# schematic.net
KiCad netlist of a schematic drawn in EasyEDA
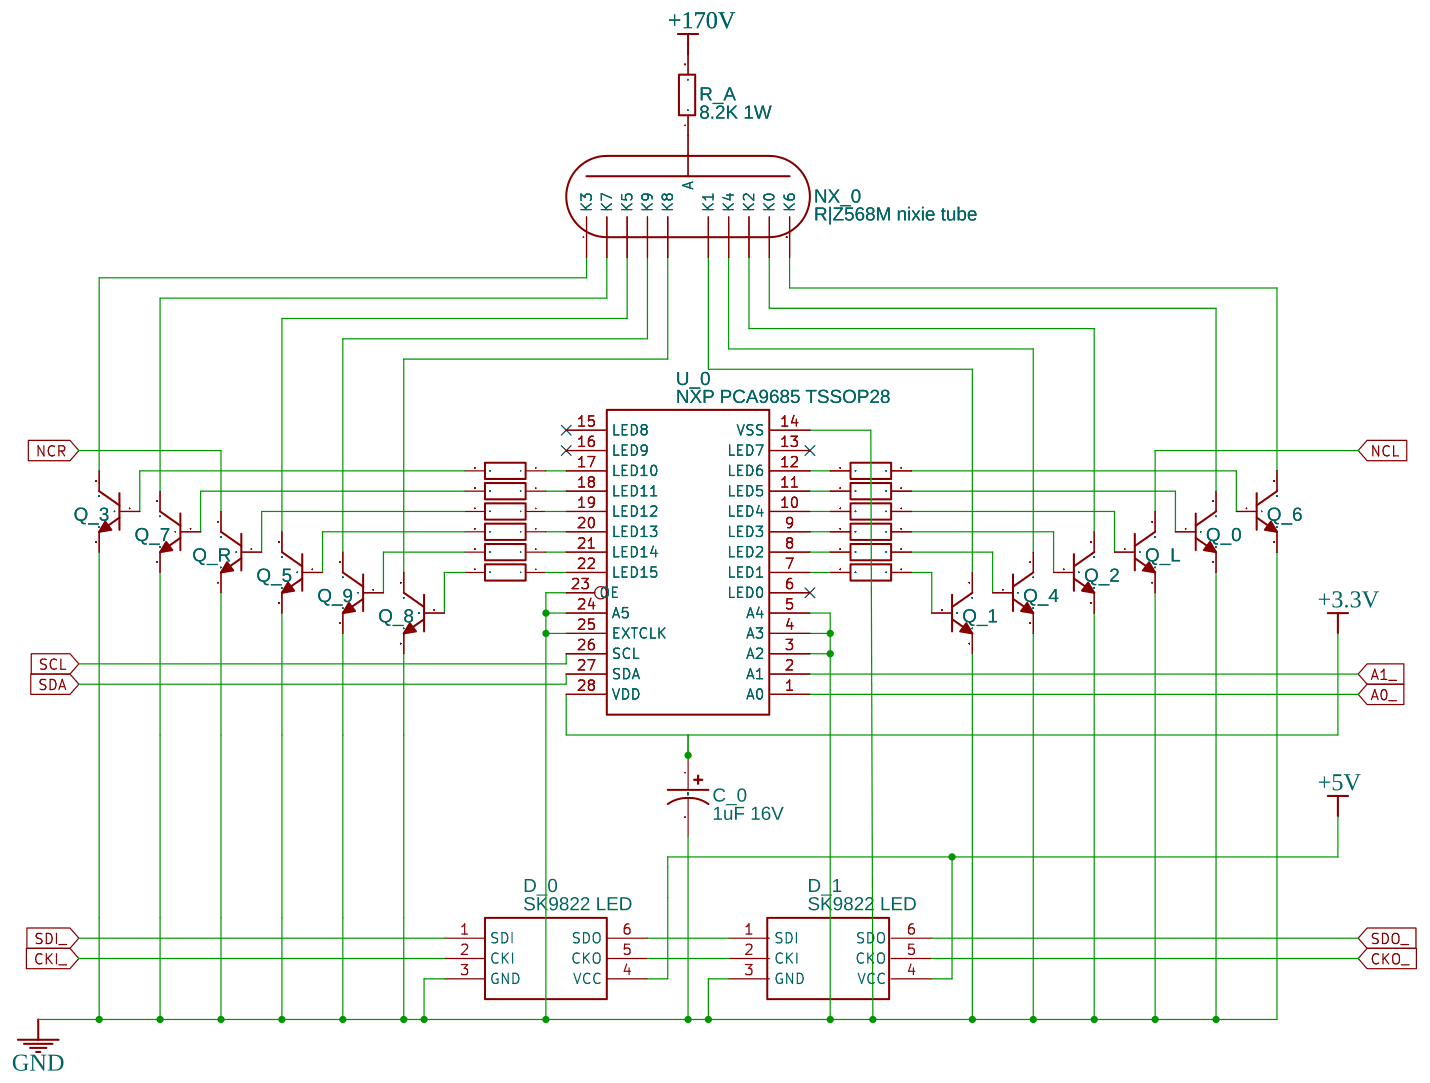
[diagram p0: schematic sheet]

(export (version "E")
  (design (tool "Eeschema 10.0.6"))
  (components
    (comp (ref "C_0")
      (value "1uF 16V")
      (fields
        (field (name "BOM_Manufacturer Part") "C0603C105K8RACTU")
        (field (name "BOM_Supplier Part") "399-11133-1-ND")
      )
      (libsource (lib "") (part "C_Tan_SMD_A_US"))
    )
    (comp (ref "D_0")
      (value "SK9822 LED")
      (fields (field (name "BOM_Manufacturer Part") "2343") (field (name "BOM_Supplier Part") "1528-1436-ND"))
      (libsource (lib "") (part "SK9822 LED"))
    )
    (comp (ref "D_1")
      (value "SK9822 LED")
      (fields (field (name "BOM_Manufacturer Part") "2343") (field (name "BOM_Supplier Part") "1528-1436-ND"))
      (libsource (lib "") (part "SK9822 LED_1"))
    )
    (comp (ref "NX_0") (value "R|Z568M nixie tube") (libsource (lib "") (part "R|Z568M nixie tube")))
    (comp (ref "Q_0")
      (value "SMMBTA42LT1G")
      (fields (field (name "BOM_Supplier Part") "SMMBTA42LT1GOSCT-ND"))
      (libsource (lib "") (part "MMBTA42LT1G"))
    )
    (comp (ref "Q_1")
      (value "SMMBTA42LT1G")
      (fields (field (name "BOM_Supplier Part") "SMMBTA42LT1GOSCT-ND"))
      (libsource (lib "") (part "MMBTA42LT1G"))
    )
    (comp (ref "Q_2")
      (value "SMMBTA42LT1G")
      (fields (field (name "BOM_Supplier Part") "SMMBTA42LT1GOSCT-ND"))
      (libsource (lib "") (part "MMBTA42LT1G"))
    )
    (comp (ref "Q_3")
      (value "SMMBTA42LT1G")
      (fields (field (name "BOM_Supplier Part") "SMMBTA42LT1GOSCT-ND"))
      (libsource (lib "") (part "MMBTA42LT1G_2"))
    )
    (comp (ref "Q_4")
      (value "SMMBTA42LT1G")
      (fields (field (name "BOM_Supplier Part") "SMMBTA42LT1GOSCT-ND"))
      (libsource (lib "") (part "MMBTA42LT1G"))
    )
    (comp (ref "Q_5")
      (value "SMMBTA42LT1G")
      (fields (field (name "BOM_Supplier Part") "SMMBTA42LT1GOSCT-ND"))
      (libsource (lib "") (part "MMBTA42LT1G_2"))
    )
    (comp (ref "Q_6")
      (value "SMMBTA42LT1G")
      (fields (field (name "BOM_Supplier Part") "SMMBTA42LT1GOSCT-ND"))
      (libsource (lib "") (part "MMBTA42LT1G"))
    )
    (comp (ref "Q_7")
      (value "SMMBTA42LT1G")
      (fields (field (name "BOM_Supplier Part") "SMMBTA42LT1GOSCT-ND"))
      (libsource (lib "") (part "MMBTA42LT1G_2"))
    )
    (comp (ref "Q_8")
      (value "SMMBTA42LT1G")
      (fields (field (name "BOM_Supplier Part") "SMMBTA42LT1GOSCT-ND"))
      (libsource (lib "") (part "MMBTA42LT1G_2"))
    )
    (comp (ref "Q_9")
      (value "SMMBTA42LT1G")
      (fields (field (name "BOM_Supplier Part") "SMMBTA42LT1GOSCT-ND"))
      (libsource (lib "") (part "MMBTA42LT1G_2"))
    )
    (comp (ref "Q_L")
      (value "SMMBTA42LT1G")
      (fields (field (name "BOM_Supplier Part") "SMMBTA42LT1GOSCT-ND"))
      (libsource (lib "") (part "MMBTA42LT1G_3"))
    )
    (comp (ref "Q_R")
      (value "SMMBTA42LT1G")
      (fields (field (name "BOM_Supplier Part") "SMMBTA42LT1GOSCT-ND"))
      (libsource (lib "") (part "MMBTA42LT1G_1"))
    )
    (comp (ref "R_0")
      (value "1K 1/10W")
      (fields
        (field (name "BOM_Manufacturer Part") "CRCW06031K00FKEA")
        (field (name "BOM_Supplier Part") "541-1.00KHCT-ND")
      )
      (libsource (lib "") (part "CR0805-FX-1001ELF"))
    )
    (comp (ref "R_1")
      (value "1K 1/10W")
      (fields
        (field (name "BOM_Manufacturer Part") "CRCW06031K00FKEA")
        (field (name "BOM_Supplier Part") "541-1.00KHCT-ND")
      )
      (libsource (lib "") (part "CR0805-FX-1001ELF"))
    )
    (comp (ref "R_2")
      (value "1K 1/10W")
      (fields
        (field (name "BOM_Manufacturer Part") "CRCW06031K00FKEA")
        (field (name "BOM_Supplier Part") "541-1.00KHCT-ND")
      )
      (libsource (lib "") (part "CR0805-FX-1001ELF"))
    )
    (comp (ref "R_3")
      (value "1K 1/10W")
      (fields
        (field (name "BOM_Manufacturer Part") "CRCW06031K00FKEA")
        (field (name "BOM_Supplier Part") "541-1.00KHCT-ND")
      )
      (libsource (lib "") (part "CR0805-FX-1001ELF"))
    )
    (comp (ref "R_4")
      (value "1K 1/10W")
      (fields
        (field (name "BOM_Manufacturer Part") "CRCW06031K00FKEA")
        (field (name "BOM_Supplier Part") "541-1.00KHCT-ND")
      )
      (libsource (lib "") (part "CR0805-FX-1001ELF"))
    )
    (comp (ref "R_5")
      (value "1K 1/10W")
      (fields
        (field (name "BOM_Manufacturer Part") "CRCW06031K00FKEA")
        (field (name "BOM_Supplier Part") "541-1.00KHCT-ND")
      )
      (libsource (lib "") (part "CR0805-FX-1001ELF"))
    )
    (comp (ref "R_6")
      (value "1K 1/10W")
      (fields
        (field (name "BOM_Manufacturer Part") "CRCW06031K00FKEA")
        (field (name "BOM_Supplier Part") "541-1.00KHCT-ND")
      )
      (libsource (lib "") (part "CR0805-FX-1001ELF"))
    )
    (comp (ref "R_7")
      (value "1K 1/10W")
      (fields
        (field (name "BOM_Manufacturer Part") "CRCW06031K00FKEA")
        (field (name "BOM_Supplier Part") "541-1.00KHCT-ND")
      )
      (libsource (lib "") (part "CR0805-FX-1001ELF"))
    )
    (comp (ref "R_8")
      (value "1K 1/10W")
      (fields
        (field (name "BOM_Manufacturer Part") "CRCW06031K00FKEA")
        (field (name "BOM_Supplier Part") "541-1.00KHCT-ND")
      )
      (libsource (lib "") (part "CR0805-FX-1001ELF"))
    )
    (comp (ref "R_9")
      (value "1K 1/10W")
      (fields
        (field (name "BOM_Manufacturer Part") "CRCW06031K00FKEA")
        (field (name "BOM_Supplier Part") "541-1.00KHCT-ND")
      )
      (libsource (lib "") (part "CR0805-FX-1001ELF"))
    )
    (comp (ref "R_A")
      (value "8.2K 1W")
      (fields
        (field (name "BOM_Manufacturer Part") "CRCW25128K20JNEG")
        (field (name "BOM_Supplier Part") "541-8.2KXCT-ND")
      )
      (libsource (lib "") (part "CR2512F8K2E04"))
    )
    (comp (ref "R_L")
      (value "1K 1/10W")
      (fields
        (field (name "BOM_Manufacturer Part") "CRCW06031K00FKEA")
        (field (name "BOM_Supplier Part") "541-1.00KHCT-ND")
      )
      (libsource (lib "") (part "CR0805-FX-1001ELF_1"))
    )
    (comp (ref "R_R")
      (value "1K 1/10W")
      (fields
        (field (name "BOM_Manufacturer Part") "CRCW06031K00FKEA")
        (field (name "BOM_Supplier Part") "541-1.00KHCT-ND")
      )
      (libsource (lib "") (part "CR0805-FX-1001ELF_2"))
    )
    (comp (ref "U_0")
      (value "NXP PCA9685 TSSOP28")
      (fields
        (field (name "BOM_Manufacturer Part") "PCA9685PW/Q900,118")
        (field (name "BOM_Supplier Part") "568-5931-1-ND")
      )
      (libsource (lib "") (part "NXP PCA9685 TSSOP28"))
    )
  )
  (nets
    (net (code "1") (name "+3.3V") (class "Default")
      (node (ref "C_0") (pin "1") (pinfunction "1_1") (pintype "unspecified"))
      (node (ref "U_0") (pin "28") (pinfunction "VDD_28") (pintype "unspecified"))
    )
    (net (code "2") (name "+5V") (class "Default")
      (node (ref "D_0") (pin "4") (pinfunction "VCC_4") (pintype "unspecified"))
      (node (ref "D_1") (pin "4") (pinfunction "VCC_4") (pintype "unspecified"))
    )
    (net (code "3") (name "+170V") (class "Default")
      (node (ref "R_A") (pin "2") (pinfunction "2_2") (pintype "unspecified"))
    )
    (net (code "4") (name "A0_") (class "Default")
      (node (ref "U_0") (pin "1") (pinfunction "A0_1") (pintype "unspecified"))
    )
    (net (code "5") (name "A1_") (class "Default")
      (node (ref "U_0") (pin "2") (pinfunction "A1_2") (pintype "unspecified"))
    )
    (net (code "6") (name "CKI_") (class "Default")
      (node (ref "D_0") (pin "2") (pinfunction "CKI_2") (pintype "unspecified"))
    )
    (net (code "7") (name "CKO_") (class "Default")
      (node (ref "D_1") (pin "5") (pinfunction "CKO_5") (pintype "unspecified"))
    )
    (net (code "8") (name "GND") (class "Default")
      (node (ref "C_0") (pin "2") (pinfunction "2_2") (pintype "unspecified"))
      (node (ref "D_0") (pin "3") (pinfunction "GND_3") (pintype "unspecified"))
      (node (ref "D_1") (pin "3") (pinfunction "GND_3") (pintype "unspecified"))
      (node (ref "Q_0") (pin "2") (pinfunction "2_2") (pintype "input"))
      (node (ref "Q_1") (pin "2") (pinfunction "2_2") (pintype "input"))
      (node (ref "Q_2") (pin "2") (pinfunction "2_2") (pintype "input"))
      (node (ref "Q_3") (pin "2") (pinfunction "2_2") (pintype "input"))
      (node (ref "Q_4") (pin "2") (pinfunction "2_2") (pintype "input"))
      (node (ref "Q_5") (pin "2") (pinfunction "2_2") (pintype "input"))
      (node (ref "Q_6") (pin "2") (pinfunction "2_2") (pintype "input"))
      (node (ref "Q_7") (pin "2") (pinfunction "2_2") (pintype "input"))
      (node (ref "Q_8") (pin "2") (pinfunction "2_2") (pintype "input"))
      (node (ref "Q_9") (pin "2") (pinfunction "2_2") (pintype "input"))
      (node (ref "Q_L") (pin "2") (pinfunction "2_2") (pintype "input"))
      (node (ref "Q_R") (pin "2") (pinfunction "2_2") (pintype "input"))
      (node (ref "U_0") (pin "14") (pinfunction "VSS_14") (pintype "unspecified"))
      (node (ref "U_0") (pin "23") (pinfunction "OE_23") (pintype "unspecified"))
      (node (ref "U_0") (pin "24") (pinfunction "A5_24") (pintype "unspecified"))
      (node (ref "U_0") (pin "25") (pinfunction "EXTCLK_25") (pintype "unspecified"))
      (node (ref "U_0") (pin "3") (pinfunction "A2_3") (pintype "unspecified"))
      (node (ref "U_0") (pin "4") (pinfunction "A3_4") (pintype "unspecified"))
      (node (ref "U_0") (pin "5") (pinfunction "A4_5") (pintype "unspecified"))
    )
    (net (code "9") (name "NCL") (class "Default")
      (node (ref "Q_L") (pin "3") (pinfunction "3_3") (pintype "input"))
    )
    (net (code "10") (name "NCR") (class "Default")
      (node (ref "Q_R") (pin "3") (pinfunction "3_3") (pintype "input"))
    )
    (net (code "11") (name "Net-(D_0-CKO)") (class "Default")
      (node (ref "D_0") (pin "5") (pinfunction "CKO_5") (pintype "unspecified"))
      (node (ref "D_1") (pin "2") (pinfunction "CKI_2") (pintype "unspecified"))
    )
    (net (code "12") (name "Net-(D_0-SDO)") (class "Default")
      (node (ref "D_0") (pin "6") (pinfunction "SDO_6") (pintype "unspecified"))
      (node (ref "D_1") (pin "1") (pinfunction "SDI_1") (pintype "unspecified"))
    )
    (net (code "13") (name "Net-(NX_0-A)") (class "Default")
      (node (ref "NX_0") (pin "6") (pinfunction "A_6") (pintype "unspecified"))
      (node (ref "R_A") (pin "1") (pinfunction "1_1") (pintype "unspecified"))
    )
    (net (code "14") (name "Net-(NX_0-K0)") (class "Default")
      (node (ref "NX_0") (pin "4") (pinfunction "K0_4") (pintype "unspecified"))
      (node (ref "Q_0") (pin "3") (pinfunction "3_3") (pintype "input"))
    )
    (net (code "15") (name "Net-(NX_0-K1)") (class "Default")
      (node (ref "NX_0") (pin "1") (pinfunction "K1_1") (pintype "passive"))
      (node (ref "Q_1") (pin "3") (pinfunction "3_3") (pintype "input"))
    )
    (net (code "16") (name "Net-(NX_0-K2)") (class "Default")
      (node (ref "NX_0") (pin "3") (pinfunction "K2_3") (pintype "unspecified"))
      (node (ref "Q_2") (pin "3") (pinfunction "3_3") (pintype "input"))
    )
    (net (code "17") (name "Net-(NX_0-K3)") (class "Default")
      (node (ref "NX_0") (pin "7") (pinfunction "K3_7") (pintype "unspecified"))
      (node (ref "Q_3") (pin "3") (pinfunction "3_3") (pintype "input"))
    )
    (net (code "18") (name "Net-(NX_0-K4)") (class "Default")
      (node (ref "NX_0") (pin "2") (pinfunction "K4_2") (pintype "unspecified"))
      (node (ref "Q_4") (pin "3") (pinfunction "3_3") (pintype "input"))
    )
    (net (code "19") (name "Net-(NX_0-K5)") (class "Default")
      (node (ref "NX_0") (pin "9") (pinfunction "K5_9") (pintype "unspecified"))
      (node (ref "Q_5") (pin "3") (pinfunction "3_3") (pintype "input"))
    )
    (net (code "20") (name "Net-(NX_0-K6)") (class "Default")
      (node (ref "NX_0") (pin "5") (pinfunction "K6_5") (pintype "unspecified"))
      (node (ref "Q_6") (pin "3") (pinfunction "3_3") (pintype "input"))
    )
    (net (code "21") (name "Net-(NX_0-K7)") (class "Default")
      (node (ref "NX_0") (pin "8") (pinfunction "K7_8") (pintype "unspecified"))
      (node (ref "Q_7") (pin "3") (pinfunction "3_3") (pintype "input"))
    )
    (net (code "22") (name "Net-(NX_0-K8)") (class "Default")
      (node (ref "NX_0") (pin "11") (pinfunction "K8_11") (pintype "unspecified"))
      (node (ref "Q_8") (pin "3") (pinfunction "3_3") (pintype "input"))
    )
    (net (code "23") (name "Net-(NX_0-K9)") (class "Default")
      (node (ref "NX_0") (pin "10") (pinfunction "K9_10") (pintype "unspecified"))
      (node (ref "Q_9") (pin "3") (pinfunction "3_3") (pintype "input"))
    )
    (net (code "24") (name "Net-(Q_0-Pad1)") (class "Default")
      (node (ref "Q_0") (pin "1") (pinfunction "1_1") (pintype "input"))
      (node (ref "R_0") (pin "1") (pinfunction "1_1") (pintype "unspecified"))
    )
    (net (code "25") (name "Net-(Q_1-Pad1)") (class "Default")
      (node (ref "Q_1") (pin "1") (pinfunction "1_1") (pintype "input"))
      (node (ref "R_1") (pin "1") (pinfunction "1_1") (pintype "unspecified"))
    )
    (net (code "26") (name "Net-(Q_2-Pad1)") (class "Default")
      (node (ref "Q_2") (pin "1") (pinfunction "1_1") (pintype "input"))
      (node (ref "R_2") (pin "1") (pinfunction "1_1") (pintype "unspecified"))
    )
    (net (code "27") (name "Net-(Q_3-Pad1)") (class "Default")
      (node (ref "Q_3") (pin "1") (pinfunction "1_1") (pintype "input"))
      (node (ref "R_3") (pin "2") (pinfunction "2_2") (pintype "unspecified"))
    )
    (net (code "28") (name "Net-(Q_4-Pad1)") (class "Default")
      (node (ref "Q_4") (pin "1") (pinfunction "1_1") (pintype "input"))
      (node (ref "R_4") (pin "1") (pinfunction "1_1") (pintype "unspecified"))
    )
    (net (code "29") (name "Net-(Q_5-Pad1)") (class "Default")
      (node (ref "Q_5") (pin "1") (pinfunction "1_1") (pintype "input"))
      (node (ref "R_5") (pin "2") (pinfunction "2_2") (pintype "unspecified"))
    )
    (net (code "30") (name "Net-(Q_6-Pad1)") (class "Default")
      (node (ref "Q_6") (pin "1") (pinfunction "1_1") (pintype "input"))
      (node (ref "R_6") (pin "1") (pinfunction "1_1") (pintype "unspecified"))
    )
    (net (code "31") (name "Net-(Q_7-Pad1)") (class "Default")
      (node (ref "Q_7") (pin "1") (pinfunction "1_1") (pintype "input"))
      (node (ref "R_7") (pin "2") (pinfunction "2_2") (pintype "unspecified"))
    )
    (net (code "32") (name "Net-(Q_8-Pad1)") (class "Default")
      (node (ref "Q_8") (pin "1") (pinfunction "1_1") (pintype "input"))
      (node (ref "R_8") (pin "2") (pinfunction "2_2") (pintype "unspecified"))
    )
    (net (code "33") (name "Net-(Q_9-Pad1)") (class "Default")
      (node (ref "Q_9") (pin "1") (pinfunction "1_1") (pintype "input"))
      (node (ref "R_9") (pin "2") (pinfunction "2_2") (pintype "unspecified"))
    )
    (net (code "34") (name "Net-(Q_L-Pad1)") (class "Default")
      (node (ref "Q_L") (pin "1") (pinfunction "1_1") (pintype "input"))
      (node (ref "R_L") (pin "1") (pinfunction "1_1") (pintype "unspecified"))
    )
    (net (code "35") (name "Net-(Q_R-Pad1)") (class "Default")
      (node (ref "Q_R") (pin "1") (pinfunction "1_1") (pintype "input"))
      (node (ref "R_R") (pin "2") (pinfunction "2_2") (pintype "unspecified"))
    )
    (net (code "36") (name "Net-(U_0-LED1)") (class "Default")
      (node (ref "R_1") (pin "2") (pinfunction "2_2") (pintype "unspecified"))
      (node (ref "U_0") (pin "7") (pinfunction "LED1_7") (pintype "unspecified"))
    )
    (net (code "37") (name "Net-(U_0-LED2)") (class "Default")
      (node (ref "R_4") (pin "2") (pinfunction "2_2") (pintype "unspecified"))
      (node (ref "U_0") (pin "8") (pinfunction "LED2_8") (pintype "unspecified"))
    )
    (net (code "38") (name "Net-(U_0-LED3)") (class "Default")
      (node (ref "R_2") (pin "2") (pinfunction "2_2") (pintype "unspecified"))
      (node (ref "U_0") (pin "9") (pinfunction "LED3_9") (pintype "unspecified"))
    )
    (net (code "39") (name "Net-(U_0-LED4)") (class "Default")
      (node (ref "R_L") (pin "2") (pinfunction "2_2") (pintype "unspecified"))
      (node (ref "U_0") (pin "10") (pinfunction "LED4_10") (pintype "unspecified"))
    )
    (net (code "40") (name "Net-(U_0-LED5)") (class "Default")
      (node (ref "R_0") (pin "2") (pinfunction "2_2") (pintype "unspecified"))
      (node (ref "U_0") (pin "11") (pinfunction "LED5_11") (pintype "unspecified"))
    )
    (net (code "41") (name "Net-(U_0-LED6)") (class "Default")
      (node (ref "R_6") (pin "2") (pinfunction "2_2") (pintype "unspecified"))
      (node (ref "U_0") (pin "12") (pinfunction "LED6_12") (pintype "unspecified"))
    )
    (net (code "42") (name "Net-(U_0-LED10)") (class "Default")
      (node (ref "R_3") (pin "1") (pinfunction "1_1") (pintype "unspecified"))
      (node (ref "U_0") (pin "17") (pinfunction "LED10_17") (pintype "unspecified"))
    )
    (net (code "43") (name "Net-(U_0-LED11)") (class "Default")
      (node (ref "R_7") (pin "1") (pinfunction "1_1") (pintype "unspecified"))
      (node (ref "U_0") (pin "18") (pinfunction "LED11_18") (pintype "unspecified"))
    )
    (net (code "44") (name "Net-(U_0-LED12)") (class "Default")
      (node (ref "R_R") (pin "1") (pinfunction "1_1") (pintype "unspecified"))
      (node (ref "U_0") (pin "19") (pinfunction "LED12_19") (pintype "unspecified"))
    )
    (net (code "45") (name "Net-(U_0-LED13)") (class "Default")
      (node (ref "R_5") (pin "1") (pinfunction "1_1") (pintype "unspecified"))
      (node (ref "U_0") (pin "20") (pinfunction "LED13_20") (pintype "unspecified"))
    )
    (net (code "46") (name "Net-(U_0-LED14)") (class "Default")
      (node (ref "R_9") (pin "1") (pinfunction "1_1") (pintype "unspecified"))
      (node (ref "U_0") (pin "21") (pinfunction "LED14_21") (pintype "unspecified"))
    )
    (net (code "47") (name "Net-(U_0-LED15)") (class "Default")
      (node (ref "R_8") (pin "1") (pinfunction "1_1") (pintype "unspecified"))
      (node (ref "U_0") (pin "22") (pinfunction "LED15_22") (pintype "unspecified"))
    )
    (net (code "48") (name "SCL") (class "Default")
      (node (ref "U_0") (pin "26") (pinfunction "SCL_26") (pintype "unspecified"))
    )
    (net (code "49") (name "SDA") (class "Default")
      (node (ref "U_0") (pin "27") (pinfunction "SDA_27") (pintype "unspecified"))
    )
    (net (code "50") (name "SDI_") (class "Default")
      (node (ref "D_0") (pin "1") (pinfunction "SDI_1") (pintype "unspecified"))
    )
    (net (code "51") (name "SDO_") (class "Default")
      (node (ref "D_1") (pin "6") (pinfunction "SDO_6") (pintype "unspecified"))
    )
    (net (code "52") (name "unconnected-(U_0-LED0-Pad6)") (class "Default")
      (node (ref "U_0") (pin "6") (pinfunction "LED0_6") (pintype "unspecified+no_connect"))
    )
    (net (code "53") (name "unconnected-(U_0-LED7-Pad13)") (class "Default")
      (node (ref "U_0") (pin "13") (pinfunction "LED7_13") (pintype "unspecified+no_connect"))
    )
    (net (code "54") (name "unconnected-(U_0-LED8-Pad15)") (class "Default")
      (node (ref "U_0") (pin "15") (pinfunction "LED8_15") (pintype "unspecified+no_connect"))
    )
    (net (code "55") (name "unconnected-(U_0-LED9-Pad16)") (class "Default")
      (node (ref "U_0") (pin "16") (pinfunction "LED9_16") (pintype "unspecified+no_connect"))
    )
  )
)
